# MicroUSB.net
KiCad netlist of a schematic drawn in Altium Designer
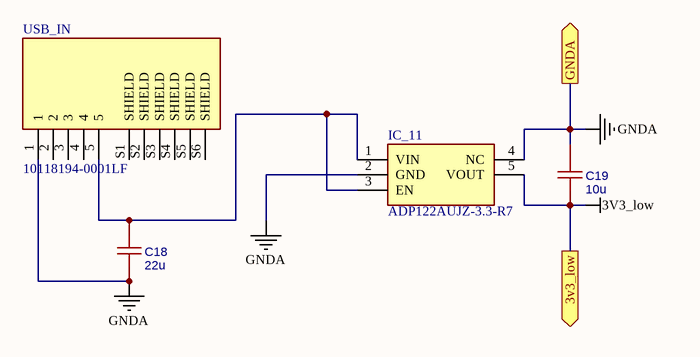
[diagram p0: MicroUSB.SchDoc]

(export (version "E")
  (design (tool "Eeschema 10.0.6"))
  (components
    (comp (ref "C18")
      (value "22u")
      (footprint "GRM31C5C1E104GA01L:CAPC3216X190")
      (libsource (lib "altium-import") (part "root_0_100nF_"))
    )
    (comp (ref "C19")
      (value "10u")
      (footprint "GRM31C5C1E104GA01L:CAPC3216X190")
      (libsource (lib "altium-import") (part "root_0_100nF_"))
    )
    (comp (ref "IC_11")
      (value "ADP122AUJZ-3.3-R7")
      (footprint "SamacSys:SOT95P280X100-5N")
      (description "Integrated Circuit")
      (fields (field (name "MOUSER PART NUMBER") "584-ADP122AUJZ-3.3R7"))
      (libsource (lib "*") (part "ADP122AUJZ-3.3-R7"))
    )
    (comp (ref "USB_IN")
      (value "10118194-0001LF")
      (footprint "AMPHENOL_10118194-0001LF")
      (description "USB - micro B USB 2.0 Receptacle Connector 5 Position Surface Mount, Right Angle; Through Hole")
      (fields (field (name "MF") "Amphenol ICC"))
      (libsource (lib "10118194-0001LF") (part "10118194-0001LF"))
    )
  )
  (nets
    (net (code "1") (name "3V3_low") (class "Default")
      (node (ref "C19") (pin "1") (pinfunction "1_1") (pintype "passive"))
      (node (ref "IC_11") (pin "5") (pinfunction "VOUT_5") (pintype "passive"))
    )
    (net (code "2") (name "GNDA") (class "Default")
      (node (ref "C18") (pin "1") (pinfunction "1_1") (pintype "passive"))
      (node (ref "C19") (pin "2") (pinfunction "2_2") (pintype "passive"))
      (node (ref "IC_11") (pin "2") (pinfunction "GND_2") (pintype "passive"))
      (node (ref "IC_11") (pin "4") (pinfunction "NC_4") (pintype "passive"))
      (node (ref "USB_IN") (pin "1") (pinfunction "1_1") (pintype "passive"))
    )
    (net (code "3") (name "Net-(IC_11-EN)") (class "Default")
      (node (ref "C18") (pin "2") (pinfunction "2_2") (pintype "passive"))
      (node (ref "IC_11") (pin "1") (pinfunction "VIN_1") (pintype "passive"))
      (node (ref "IC_11") (pin "3") (pinfunction "EN_3") (pintype "passive"))
      (node (ref "USB_IN") (pin "5") (pinfunction "5_5") (pintype "passive"))
    )
    (net (code "4") (name "unconnected-(USB_IN-Pad2)") (class "Default")
      (node (ref "USB_IN") (pin "2") (pinfunction "2_2") (pintype "passive"))
    )
    (net (code "5") (name "unconnected-(USB_IN-Pad3)") (class "Default")
      (node (ref "USB_IN") (pin "3") (pinfunction "3_3") (pintype "passive"))
    )
    (net (code "6") (name "unconnected-(USB_IN-Pad4)") (class "Default")
      (node (ref "USB_IN") (pin "4") (pinfunction "4_4") (pintype "passive"))
    )
    (net (code "7") (name "unconnected-(USB_IN-SHIELD-PadS1)") (class "Default")
      (node (ref "USB_IN") (pin "S1") (pinfunction "SHIELD_S1") (pintype "passive"))
    )
    (net (code "8") (name "unconnected-(USB_IN-SHIELD-PadS2)") (class "Default")
      (node (ref "USB_IN") (pin "S2") (pinfunction "SHIELD_S2") (pintype "passive"))
    )
    (net (code "9") (name "unconnected-(USB_IN-SHIELD-PadS3)") (class "Default")
      (node (ref "USB_IN") (pin "S3") (pinfunction "SHIELD_S3") (pintype "passive"))
    )
    (net (code "10") (name "unconnected-(USB_IN-SHIELD-PadS4)") (class "Default")
      (node (ref "USB_IN") (pin "S4") (pinfunction "SHIELD_S4") (pintype "passive"))
    )
    (net (code "11") (name "unconnected-(USB_IN-SHIELD-PadS5)") (class "Default")
      (node (ref "USB_IN") (pin "S5") (pinfunction "SHIELD_S5") (pintype "passive"))
    )
    (net (code "12") (name "unconnected-(USB_IN-SHIELD-PadS6)") (class "Default")
      (node (ref "USB_IN") (pin "S6") (pinfunction "SHIELD_S6") (pintype "passive"))
    )
  )
)
